# usb-to-serial.net
KiCad netlist of a schematic drawn in EAGLE
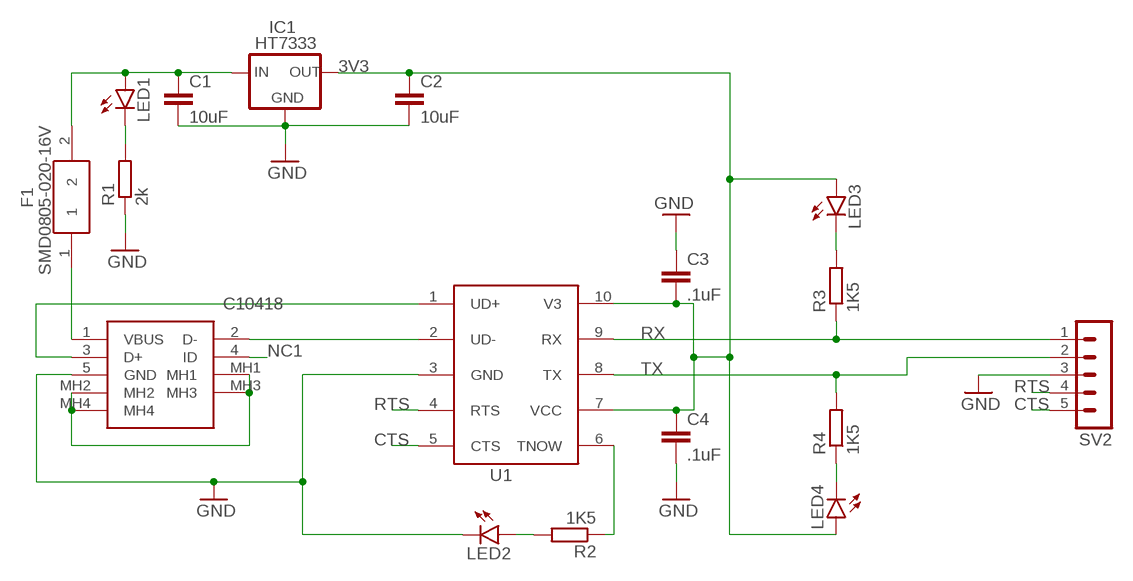
[diagram p0: schematic, sheet 1]

(export (version "E")
  (design (tool "Eeschema 10.0.6"))
  (components
    (comp (ref "C1")
      (value "10uF")
      (footprint "eagle-import:C0805")
      (libsource (lib "eagle-import") (part "C-EUC0805"))
    )
    (comp (ref "C2")
      (value "10uF")
      (footprint "eagle-import:C0805")
      (libsource (lib "eagle-import") (part "C-EUC0805"))
    )
    (comp (ref "C3")
      (value ".1uF")
      (footprint "eagle-import:C0805")
      (libsource (lib "eagle-import") (part "C-EUC0805"))
    )
    (comp (ref "C4")
      (value ".1uF")
      (footprint "eagle-import:C0805")
      (libsource (lib "eagle-import") (part "C-EUC0805"))
    )
    (comp (ref "F1")
      (value "SMD0805-020-16V")
      (footprint "eagle-import:FUSC2114X100N")
      (libsource (lib "eagle-import") (part "SMD0805-020-16V"))
    )
    (comp (ref "IC1")
      (value "HT7333")
      (footprint "eagle-import:SOT-89")
      (libsource (lib "eagle-import") (part "HT7333"))
    )
    (comp (ref "J1")
      (value "C10418")
      (footprint "eagle-import:C10418")
      (libsource (lib "eagle-import") (part "C10418"))
    )
    (comp (ref "LED1")
      (value "LEDCHIP-LED0805")
      (footprint "eagle-import:CHIP-LED0805")
      (libsource (lib "eagle-import") (part "LEDCHIP-LED0805"))
    )
    (comp (ref "LED2")
      (value "LEDCHIP-LED0805")
      (footprint "eagle-import:CHIP-LED0805")
      (libsource (lib "eagle-import") (part "LEDCHIP-LED0805"))
    )
    (comp (ref "LED3")
      (value "LEDCHIP-LED0805")
      (footprint "eagle-import:CHIP-LED0805")
      (libsource (lib "eagle-import") (part "LEDCHIP-LED0805"))
    )
    (comp (ref "LED4")
      (value "LEDCHIP-LED0805")
      (footprint "eagle-import:CHIP-LED0805")
      (libsource (lib "eagle-import") (part "LEDCHIP-LED0805"))
    )
    (comp (ref "R1")
      (value "2k")
      (footprint "eagle-import:R0805")
      (libsource (lib "eagle-import") (part "R-EU_R0805"))
    )
    (comp (ref "R2")
      (value "1K5")
      (footprint "eagle-import:R0805")
      (libsource (lib "eagle-import") (part "R-EU_R0805"))
    )
    (comp (ref "R3")
      (value "1K5")
      (footprint "eagle-import:R0805")
      (libsource (lib "eagle-import") (part "R-EU_R0805"))
    )
    (comp (ref "R4")
      (value "1K5")
      (footprint "eagle-import:R0805")
      (libsource (lib "eagle-import") (part "R-EU_R0805"))
    )
    (comp (ref "SV2")
      (value "MA05-1")
      (footprint "eagle-import:MA05-1")
      (libsource (lib "eagle-import") (part "MA05-1"))
    )
    (comp (ref "U1")
      (value "CH340ESMD")
      (footprint "eagle-import:MSOP10")
      (libsource (lib "eagle-import") (part "CH340ESMD"))
    )
  )
  (nets
    (net (code "1") (name "/3V3") (class "Default")
      (node (ref "C2") (pin "1") (pinfunction "1_1") (pintype "passive"))
      (node (ref "C3") (pin "2") (pinfunction "2_2") (pintype "passive"))
      (node (ref "C4") (pin "1") (pinfunction "1_1") (pintype "passive"))
      (node (ref "IC1") (pin "1") (pinfunction "OUT_1") (pintype "passive"))
      (node (ref "LED3") (pin "A") (pinfunction "A_A") (pintype "passive"))
      (node (ref "LED4") (pin "A") (pinfunction "A_A") (pintype "passive"))
      (node (ref "U1") (pin "10") (pinfunction "V3_10") (pintype "power_in"))
      (node (ref "U1") (pin "7") (pinfunction "VCC_7") (pintype "power_in"))
    )
    (net (code "2") (name "/CTS") (class "Default")
      (node (ref "SV2") (pin "5") (pinfunction "5_5") (pintype "passive"))
      (node (ref "U1") (pin "5") (pinfunction "CTS_5") (pintype "input"))
    )
    (net (code "3") (name "/NC1") (class "Default")
      (node (ref "J1") (pin "4") (pinfunction "ID_4") (pintype "bidirectional"))
    )
    (net (code "4") (name "/RTS") (class "Default")
      (node (ref "SV2") (pin "4") (pinfunction "4_4") (pintype "passive"))
      (node (ref "U1") (pin "4") (pinfunction "RTS_4") (pintype "output"))
    )
    (net (code "5") (name "/RX") (class "Default")
      (node (ref "R3") (pin "1") (pinfunction "1_1") (pintype "passive"))
      (node (ref "SV2") (pin "1") (pinfunction "1_1") (pintype "passive"))
      (node (ref "U1") (pin "9") (pinfunction "RX_9") (pintype "input"))
    )
    (net (code "6") (name "/TX") (class "Default")
      (node (ref "R4") (pin "2") (pinfunction "2_2") (pintype "passive"))
      (node (ref "SV2") (pin "2") (pinfunction "2_2") (pintype "passive"))
      (node (ref "U1") (pin "8") (pinfunction "TX_8") (pintype "output"))
    )
    (net (code "7") (name "GND") (class "Default")
      (node (ref "C1") (pin "2") (pinfunction "2_2") (pintype "passive"))
      (node (ref "C2") (pin "2") (pinfunction "2_2") (pintype "passive"))
      (node (ref "C3") (pin "1") (pinfunction "1_1") (pintype "passive"))
      (node (ref "C4") (pin "2") (pinfunction "2_2") (pintype "passive"))
      (node (ref "IC1") (pin "2") (pinfunction "GND_2") (pintype "input"))
      (node (ref "J1") (pin "5") (pinfunction "GND_5") (pintype "bidirectional"))
      (node (ref "LED2") (pin "C") (pinfunction "C_C") (pintype "passive"))
      (node (ref "R1") (pin "1") (pinfunction "1_1") (pintype "passive"))
      (node (ref "SV2") (pin "3") (pinfunction "3_3") (pintype "passive"))
      (node (ref "U1") (pin "3") (pinfunction "GND_3") (pintype "power_in"))
    )
    (net (code "8") (name "Net-(C1-Pad1)") (class "Default")
      (node (ref "C1") (pin "1") (pinfunction "1_1") (pintype "passive"))
      (node (ref "F1") (pin "2") (pinfunction "2_2") (pintype "bidirectional"))
      (node (ref "IC1") (pin "3") (pinfunction "IN_3") (pintype "input"))
      (node (ref "IC1") (pin "4") (pinfunction "IN_4") (pintype "input"))
      (node (ref "LED1") (pin "A") (pinfunction "A_A") (pintype "passive"))
    )
    (net (code "9") (name "Net-(J1-D+)") (class "Default")
      (node (ref "J1") (pin "3") (pinfunction "D+_3") (pintype "bidirectional"))
      (node (ref "U1") (pin "1") (pinfunction "UD+_1") (pintype "bidirectional"))
    )
    (net (code "10") (name "Net-(J1-D-)") (class "Default")
      (node (ref "J1") (pin "2") (pinfunction "D-_2") (pintype "bidirectional"))
      (node (ref "U1") (pin "2") (pinfunction "UD-_2") (pintype "bidirectional"))
    )
    (net (code "11") (name "Net-(J1-PadMH1)") (class "Default")
      (node (ref "J1") (pin "MH1") (pinfunction "MH1_MH1") (pintype "bidirectional"))
      (node (ref "J1") (pin "MH2") (pinfunction "MH2_MH2") (pintype "bidirectional"))
      (node (ref "J1") (pin "MH3") (pinfunction "MH3_MH3") (pintype "bidirectional"))
      (node (ref "J1") (pin "MH4") (pinfunction "MH4_MH4") (pintype "bidirectional"))
    )
    (net (code "12") (name "Net-(J1-VBUS)") (class "Default")
      (node (ref "F1") (pin "1") (pinfunction "1_1") (pintype "bidirectional"))
      (node (ref "J1") (pin "1") (pinfunction "VBUS_1") (pintype "bidirectional"))
    )
    (net (code "13") (name "Net-(LED1-PadC)") (class "Default")
      (node (ref "LED1") (pin "C") (pinfunction "C_C") (pintype "passive"))
      (node (ref "R1") (pin "2") (pinfunction "2_2") (pintype "passive"))
    )
    (net (code "14") (name "Net-(LED2-PadA)") (class "Default")
      (node (ref "LED2") (pin "A") (pinfunction "A_A") (pintype "passive"))
      (node (ref "R2") (pin "2") (pinfunction "2_2") (pintype "passive"))
    )
    (net (code "15") (name "Net-(LED3-PadC)") (class "Default")
      (node (ref "LED3") (pin "C") (pinfunction "C_C") (pintype "passive"))
      (node (ref "R3") (pin "2") (pinfunction "2_2") (pintype "passive"))
    )
    (net (code "16") (name "Net-(LED4-PadC)") (class "Default")
      (node (ref "LED4") (pin "C") (pinfunction "C_C") (pintype "passive"))
      (node (ref "R4") (pin "1") (pinfunction "1_1") (pintype "passive"))
    )
    (net (code "17") (name "Net-(U1-TNOW)") (class "Default")
      (node (ref "R2") (pin "1") (pinfunction "1_1") (pintype "passive"))
      (node (ref "U1") (pin "6") (pinfunction "TNOW_6") (pintype "output"))
    )
  )
)
